# l-drv_h2-smd-001.net
KiCad netlist of a schematic drawn in EAGLE
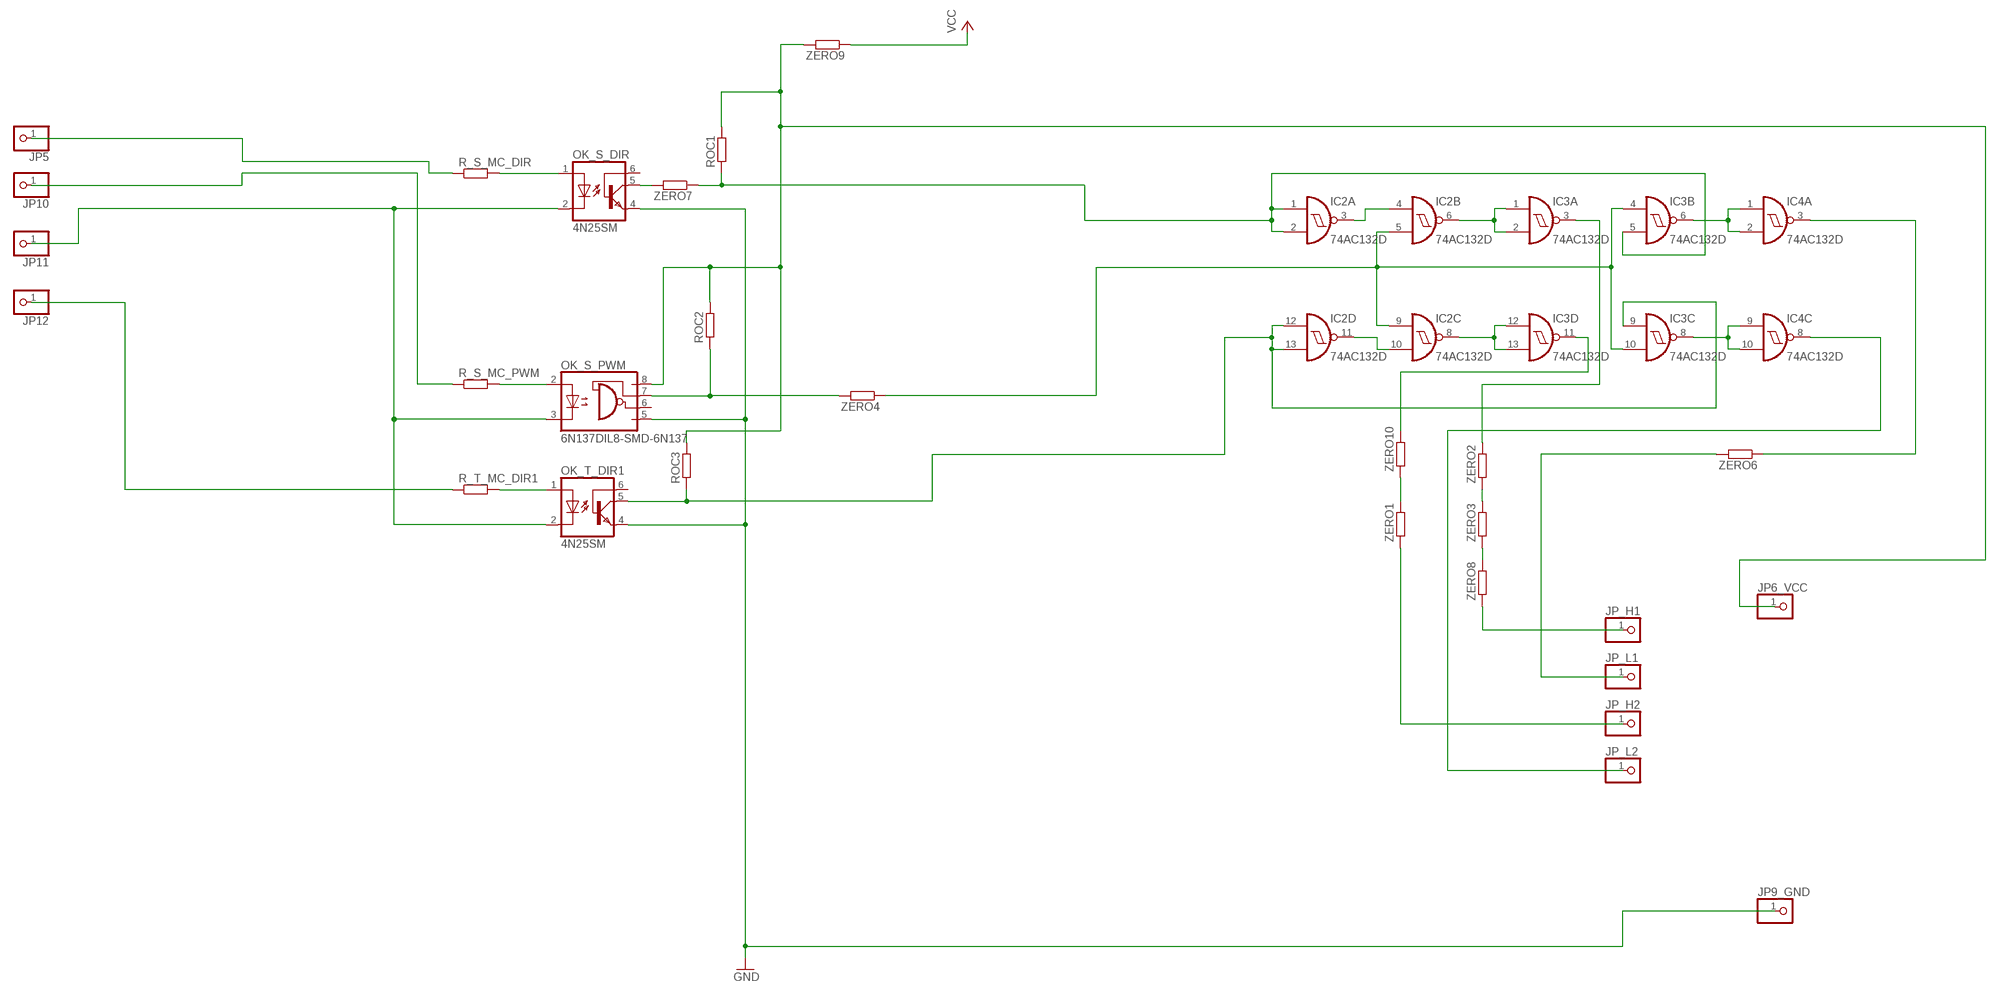
[diagram p0: schematic, sheet 1]

(export (version "E")
  (design (tool "Eeschema 10.0.6"))
  (components
    (comp (ref "IC2")
      (value "74AC132D")
      (footprint "eagle-import:SO14")
      (libsource (lib "eagle-import") (part "74132DAC"))
    )
    (comp (ref "IC3")
      (value "74AC132D")
      (footprint "eagle-import:SO14")
      (libsource (lib "eagle-import") (part "74132DAC"))
    )
    (comp (ref "IC4")
      (value "74AC132D")
      (footprint "eagle-import:SO14")
      (libsource (lib "eagle-import") (part "74132DAC"))
    )
    (comp (ref "JP5")
      (value "PINHD-1X1")
      (footprint "eagle-import:1X01")
      (libsource (lib "eagle-import") (part "PINHD-1X1"))
    )
    (comp (ref "JP6_VCC")
      (value "PINHD-1X1")
      (footprint "eagle-import:1X01")
      (libsource (lib "eagle-import") (part "PINHD-1X1"))
    )
    (comp (ref "JP9_GND")
      (value "PINHD-1X1")
      (footprint "eagle-import:1X01")
      (libsource (lib "eagle-import") (part "PINHD-1X1"))
    )
    (comp (ref "JP10")
      (value "PINHD-1X1")
      (footprint "eagle-import:1X01")
      (libsource (lib "eagle-import") (part "PINHD-1X1"))
    )
    (comp (ref "JP11")
      (value "PINHD-1X1")
      (footprint "eagle-import:1X01")
      (libsource (lib "eagle-import") (part "PINHD-1X1"))
    )
    (comp (ref "JP12")
      (value "PINHD-1X1")
      (footprint "eagle-import:1X01")
      (libsource (lib "eagle-import") (part "PINHD-1X1"))
    )
    (comp (ref "JP_H1")
      (value "PINHD-1X1")
      (footprint "eagle-import:1X01")
      (libsource (lib "eagle-import") (part "PINHD-1X1"))
    )
    (comp (ref "JP_H2")
      (value "PINHD-1X1")
      (footprint "eagle-import:1X01")
      (libsource (lib "eagle-import") (part "PINHD-1X1"))
    )
    (comp (ref "JP_L1")
      (value "PINHD-1X1")
      (footprint "eagle-import:1X01")
      (libsource (lib "eagle-import") (part "PINHD-1X1"))
    )
    (comp (ref "JP_L2")
      (value "PINHD-1X1")
      (footprint "eagle-import:1X01")
      (libsource (lib "eagle-import") (part "PINHD-1X1"))
    )
    (comp (ref "OK_S_DIR")
      (value "4N25SM")
      (footprint "eagle-import:DIL6-SMD")
      (fields (field (name "MF") "FAIRCHILD SEMICONDUCTOR"))
      (libsource (lib "eagle-import") (part "4N?MS25"))
    )
    (comp (ref "OK_S_PWM")
      (value "6N137DIL8-SMD-6N137")
      (footprint "eagle-import:DIL8-SMD")
      (libsource (lib "eagle-import") (part "6N137DIL8-SMD-6N137"))
    )
    (comp (ref "OK_T_DIR1")
      (value "4N25SM")
      (footprint "eagle-import:DIL6-SMD")
      (fields (field (name "MF") "FAIRCHILD SEMICONDUCTOR"))
      (libsource (lib "eagle-import") (part "4N?MS25"))
    )
    (comp (ref "ROC1")
      (value "R-EU_R1206")
      (footprint "eagle-import:R1206")
      (libsource (lib "eagle-import") (part "R-EU_R1206"))
    )
    (comp (ref "ROC2")
      (value "R-EU_R1206")
      (footprint "eagle-import:R1206")
      (libsource (lib "eagle-import") (part "R-EU_R1206"))
    )
    (comp (ref "ROC3")
      (value "R-EU_R1206")
      (footprint "eagle-import:R1206")
      (libsource (lib "eagle-import") (part "R-EU_R1206"))
    )
    (comp (ref "R_S_MC_DIR")
      (value "R-EU_R1206")
      (footprint "eagle-import:R1206")
      (libsource (lib "eagle-import") (part "R-EU_R1206"))
    )
    (comp (ref "R_S_MC_PWM")
      (value "R-EU_R1206")
      (footprint "eagle-import:R1206")
      (libsource (lib "eagle-import") (part "R-EU_R1206"))
    )
    (comp (ref "R_T_MC_DIR1")
      (value "R-EU_R1206")
      (footprint "eagle-import:R1206")
      (libsource (lib "eagle-import") (part "R-EU_R1206"))
    )
    (comp (ref "ZERO1")
      (value "R-EU_R1206")
      (footprint "eagle-import:R1206")
      (libsource (lib "eagle-import") (part "R-EU_R1206"))
    )
    (comp (ref "ZERO2")
      (value "R-EU_R1206")
      (footprint "eagle-import:R1206")
      (libsource (lib "eagle-import") (part "R-EU_R1206"))
    )
    (comp (ref "ZERO3")
      (value "R-EU_R1206")
      (footprint "eagle-import:R1206")
      (libsource (lib "eagle-import") (part "R-EU_R1206"))
    )
    (comp (ref "ZERO4")
      (value "R-EU_R1206")
      (footprint "eagle-import:R1206")
      (libsource (lib "eagle-import") (part "R-EU_R1206"))
    )
    (comp (ref "ZERO6")
      (value "R-EU_R1206")
      (footprint "eagle-import:R1206")
      (libsource (lib "eagle-import") (part "R-EU_R1206"))
    )
    (comp (ref "ZERO7")
      (value "R-EU_R1206")
      (footprint "eagle-import:R1206")
      (libsource (lib "eagle-import") (part "R-EU_R1206"))
    )
    (comp (ref "ZERO8")
      (value "R-EU_R1206")
      (footprint "eagle-import:R1206")
      (libsource (lib "eagle-import") (part "R-EU_R1206"))
    )
    (comp (ref "ZERO9")
      (value "R-EU_R1206")
      (footprint "eagle-import:R1206")
      (libsource (lib "eagle-import") (part "R-EU_R1206"))
    )
    (comp (ref "ZERO10")
      (value "R-EU_R1206")
      (footprint "eagle-import:R1206")
      (libsource (lib "eagle-import") (part "R-EU_R1206"))
    )
  )
  (nets
    (net (code "1") (name "GND") (class "Default")
      (node (ref "JP9_GND") (pin "1") (pinfunction "1_1") (pintype "passive"))
      (node (ref "OK_S_DIR") (pin "4") (pinfunction "EMI_4") (pintype "passive"))
      (node (ref "OK_S_PWM") (pin "5") (pinfunction "GND_5") (pintype "passive"))
      (node (ref "OK_T_DIR1") (pin "4") (pinfunction "EMI_4") (pintype "passive"))
    )
    (net (code "2") (name "Net-(IC2A-I0)") (class "Default")
      (node (ref "IC2") (pin "1") (pinfunction "I0_1") (pintype "input"))
      (node (ref "IC2") (pin "2") (pinfunction "I1_2") (pintype "input"))
      (node (ref "IC3") (pin "5") (pinfunction "I1_5") (pintype "input"))
      (node (ref "ROC1") (pin "1") (pinfunction "1_1") (pintype "passive"))
      (node (ref "ZERO7") (pin "1") (pinfunction "1_1") (pintype "passive"))
    )
    (net (code "3") (name "Net-(IC2A-O)") (class "Default")
      (node (ref "IC2") (pin "3") (pinfunction "O_3") (pintype "output"))
      (node (ref "IC2") (pin "4") (pinfunction "I0_4") (pintype "input"))
    )
    (net (code "4") (name "Net-(IC2B-I1)") (class "Default")
      (node (ref "IC2") (pin "5") (pinfunction "I1_5") (pintype "input"))
      (node (ref "IC2") (pin "9") (pinfunction "I0_9") (pintype "input"))
      (node (ref "IC3") (pin "10") (pinfunction "I1_10") (pintype "input"))
      (node (ref "IC3") (pin "4") (pinfunction "I0_4") (pintype "input"))
      (node (ref "ZERO4") (pin "1") (pinfunction "1_1") (pintype "passive"))
    )
    (net (code "5") (name "Net-(IC2B-O)") (class "Default")
      (node (ref "IC2") (pin "6") (pinfunction "O_6") (pintype "output"))
      (node (ref "IC3") (pin "1") (pinfunction "I0_1") (pintype "input"))
      (node (ref "IC3") (pin "2") (pinfunction "I1_2") (pintype "input"))
    )
    (net (code "6") (name "Net-(IC2C-I1)") (class "Default")
      (node (ref "IC2") (pin "10") (pinfunction "I1_10") (pintype "input"))
      (node (ref "IC2") (pin "11") (pinfunction "O_11") (pintype "output"))
    )
    (net (code "7") (name "Net-(IC2C-O)") (class "Default")
      (node (ref "IC2") (pin "8") (pinfunction "O_8") (pintype "output"))
      (node (ref "IC3") (pin "12") (pinfunction "I0_12") (pintype "input"))
      (node (ref "IC3") (pin "13") (pinfunction "I1_13") (pintype "input"))
    )
    (net (code "8") (name "Net-(IC2D-I0)") (class "Default")
      (node (ref "IC2") (pin "12") (pinfunction "I0_12") (pintype "input"))
      (node (ref "IC2") (pin "13") (pinfunction "I1_13") (pintype "input"))
      (node (ref "IC3") (pin "9") (pinfunction "I0_9") (pintype "input"))
      (node (ref "OK_T_DIR1") (pin "5") (pinfunction "COL_5") (pintype "passive"))
      (node (ref "ROC3") (pin "1") (pinfunction "1_1") (pintype "passive"))
    )
    (net (code "9") (name "Net-(IC3A-O)") (class "Default")
      (node (ref "IC3") (pin "3") (pinfunction "O_3") (pintype "output"))
      (node (ref "ZERO2") (pin "2") (pinfunction "2_2") (pintype "passive"))
    )
    (net (code "10") (name "Net-(IC3B-O)") (class "Default")
      (node (ref "IC3") (pin "6") (pinfunction "O_6") (pintype "output"))
      (node (ref "IC4") (pin "1") (pinfunction "I0_1") (pintype "input"))
      (node (ref "IC4") (pin "2") (pinfunction "I1_2") (pintype "input"))
    )
    (net (code "11") (name "Net-(IC3C-O)") (class "Default")
      (node (ref "IC3") (pin "8") (pinfunction "O_8") (pintype "output"))
      (node (ref "IC4") (pin "10") (pinfunction "I1_10") (pintype "input"))
      (node (ref "IC4") (pin "9") (pinfunction "I0_9") (pintype "input"))
    )
    (net (code "12") (name "Net-(IC3D-O)") (class "Default")
      (node (ref "IC3") (pin "11") (pinfunction "O_11") (pintype "output"))
      (node (ref "ZERO10") (pin "2") (pinfunction "2_2") (pintype "passive"))
    )
    (net (code "13") (name "Net-(IC4A-O)") (class "Default")
      (node (ref "IC4") (pin "3") (pinfunction "O_3") (pintype "output"))
      (node (ref "ZERO6") (pin "1") (pinfunction "1_1") (pintype "passive"))
    )
    (net (code "14") (name "Net-(IC4C-O)") (class "Default")
      (node (ref "IC4") (pin "8") (pinfunction "O_8") (pintype "output"))
      (node (ref "JP_L2") (pin "1") (pinfunction "1_1") (pintype "passive"))
    )
    (net (code "15") (name "Net-(JP5-Pad1)") (class "Default")
      (node (ref "JP5") (pin "1") (pinfunction "1_1") (pintype "passive"))
      (node (ref "R_S_MC_DIR") (pin "1") (pinfunction "1_1") (pintype "passive"))
    )
    (net (code "16") (name "Net-(JP10-Pad1)") (class "Default")
      (node (ref "JP10") (pin "1") (pinfunction "1_1") (pintype "passive"))
      (node (ref "R_S_MC_PWM") (pin "1") (pinfunction "1_1") (pintype "passive"))
    )
    (net (code "17") (name "Net-(JP12-Pad1)") (class "Default")
      (node (ref "JP12") (pin "1") (pinfunction "1_1") (pintype "passive"))
      (node (ref "R_T_MC_DIR1") (pin "1") (pinfunction "1_1") (pintype "passive"))
    )
    (net (code "18") (name "Net-(JP_H1-Pad1)") (class "Default")
      (node (ref "JP_H1") (pin "1") (pinfunction "1_1") (pintype "passive"))
      (node (ref "ZERO8") (pin "1") (pinfunction "1_1") (pintype "passive"))
    )
    (net (code "19") (name "Net-(JP_H2-Pad1)") (class "Default")
      (node (ref "JP_H2") (pin "1") (pinfunction "1_1") (pintype "passive"))
      (node (ref "ZERO1") (pin "1") (pinfunction "1_1") (pintype "passive"))
    )
    (net (code "20") (name "Net-(JP_L1-Pad1)") (class "Default")
      (node (ref "JP_L1") (pin "1") (pinfunction "1_1") (pintype "passive"))
      (node (ref "ZERO6") (pin "2") (pinfunction "2_2") (pintype "passive"))
    )
    (net (code "21") (name "Net-(OK_S_DIR-A)") (class "Default")
      (node (ref "OK_S_DIR") (pin "1") (pinfunction "A_1") (pintype "passive"))
      (node (ref "R_S_MC_DIR") (pin "2") (pinfunction "2_2") (pintype "passive"))
    )
    (net (code "22") (name "Net-(OK_S_DIR-C)") (class "Default")
      (node (ref "JP11") (pin "1") (pinfunction "1_1") (pintype "passive"))
      (node (ref "OK_S_DIR") (pin "2") (pinfunction "C_2") (pintype "passive"))
      (node (ref "OK_S_PWM") (pin "3") (pinfunction "C_3") (pintype "passive"))
      (node (ref "OK_T_DIR1") (pin "2") (pinfunction "C_2") (pintype "passive"))
    )
    (net (code "23") (name "Net-(OK_S_DIR-COL)") (class "Default")
      (node (ref "OK_S_DIR") (pin "5") (pinfunction "COL_5") (pintype "passive"))
      (node (ref "ZERO7") (pin "2") (pinfunction "2_2") (pintype "passive"))
    )
    (net (code "24") (name "Net-(OK_S_PWM-A)") (class "Default")
      (node (ref "OK_S_PWM") (pin "2") (pinfunction "A_2") (pintype "passive"))
      (node (ref "R_S_MC_PWM") (pin "2") (pinfunction "2_2") (pintype "passive"))
    )
    (net (code "25") (name "Net-(OK_S_PWM-VCC)") (class "Default")
      (node (ref "JP6_VCC") (pin "1") (pinfunction "1_1") (pintype "passive"))
      (node (ref "OK_S_PWM") (pin "8") (pinfunction "VCC_8") (pintype "passive"))
      (node (ref "ROC1") (pin "2") (pinfunction "2_2") (pintype "passive"))
      (node (ref "ROC2") (pin "2") (pinfunction "2_2") (pintype "passive"))
      (node (ref "ROC3") (pin "2") (pinfunction "2_2") (pintype "passive"))
      (node (ref "ZERO9") (pin "2") (pinfunction "2_2") (pintype "passive"))
    )
    (net (code "26") (name "Net-(OK_S_PWM-VE)") (class "Default")
      (node (ref "OK_S_PWM") (pin "7") (pinfunction "VE_7") (pintype "passive"))
      (node (ref "ROC2") (pin "1") (pinfunction "1_1") (pintype "passive"))
      (node (ref "ZERO4") (pin "2") (pinfunction "2_2") (pintype "passive"))
    )
    (net (code "27") (name "Net-(OK_T_DIR1-A)") (class "Default")
      (node (ref "OK_T_DIR1") (pin "1") (pinfunction "A_1") (pintype "passive"))
      (node (ref "R_T_MC_DIR1") (pin "2") (pinfunction "2_2") (pintype "passive"))
    )
    (net (code "28") (name "Net-(ZERO1-Pad2)") (class "Default")
      (node (ref "ZERO1") (pin "2") (pinfunction "2_2") (pintype "passive"))
      (node (ref "ZERO10") (pin "1") (pinfunction "1_1") (pintype "passive"))
    )
    (net (code "29") (name "Net-(ZERO2-Pad1)") (class "Default")
      (node (ref "ZERO2") (pin "1") (pinfunction "1_1") (pintype "passive"))
      (node (ref "ZERO3") (pin "2") (pinfunction "2_2") (pintype "passive"))
    )
    (net (code "30") (name "Net-(ZERO3-Pad1)") (class "Default")
      (node (ref "ZERO3") (pin "1") (pinfunction "1_1") (pintype "passive"))
      (node (ref "ZERO8") (pin "2") (pinfunction "2_2") (pintype "passive"))
    )
    (net (code "31") (name "VCC") (class "Default")
      (node (ref "ZERO9") (pin "1") (pinfunction "1_1") (pintype "passive"))
    )
    (net (code "32") (name "unconnected-(OK_S_DIR-BAS-Pad6)") (class "Default")
      (node (ref "OK_S_DIR") (pin "6") (pinfunction "BAS_6") (pintype "passive"))
    )
    (net (code "33") (name "unconnected-(OK_S_PWM-VO-Pad6)") (class "Default")
      (node (ref "OK_S_PWM") (pin "6") (pinfunction "VO_6") (pintype "passive"))
    )
    (net (code "34") (name "unconnected-(OK_T_DIR1-BAS-Pad6)") (class "Default")
      (node (ref "OK_T_DIR1") (pin "6") (pinfunction "BAS_6") (pintype "passive"))
    )
  )
)
